# shiftpwm_tlc5916_SMD_RGB.net
KiCad netlist of a schematic drawn in EAGLE
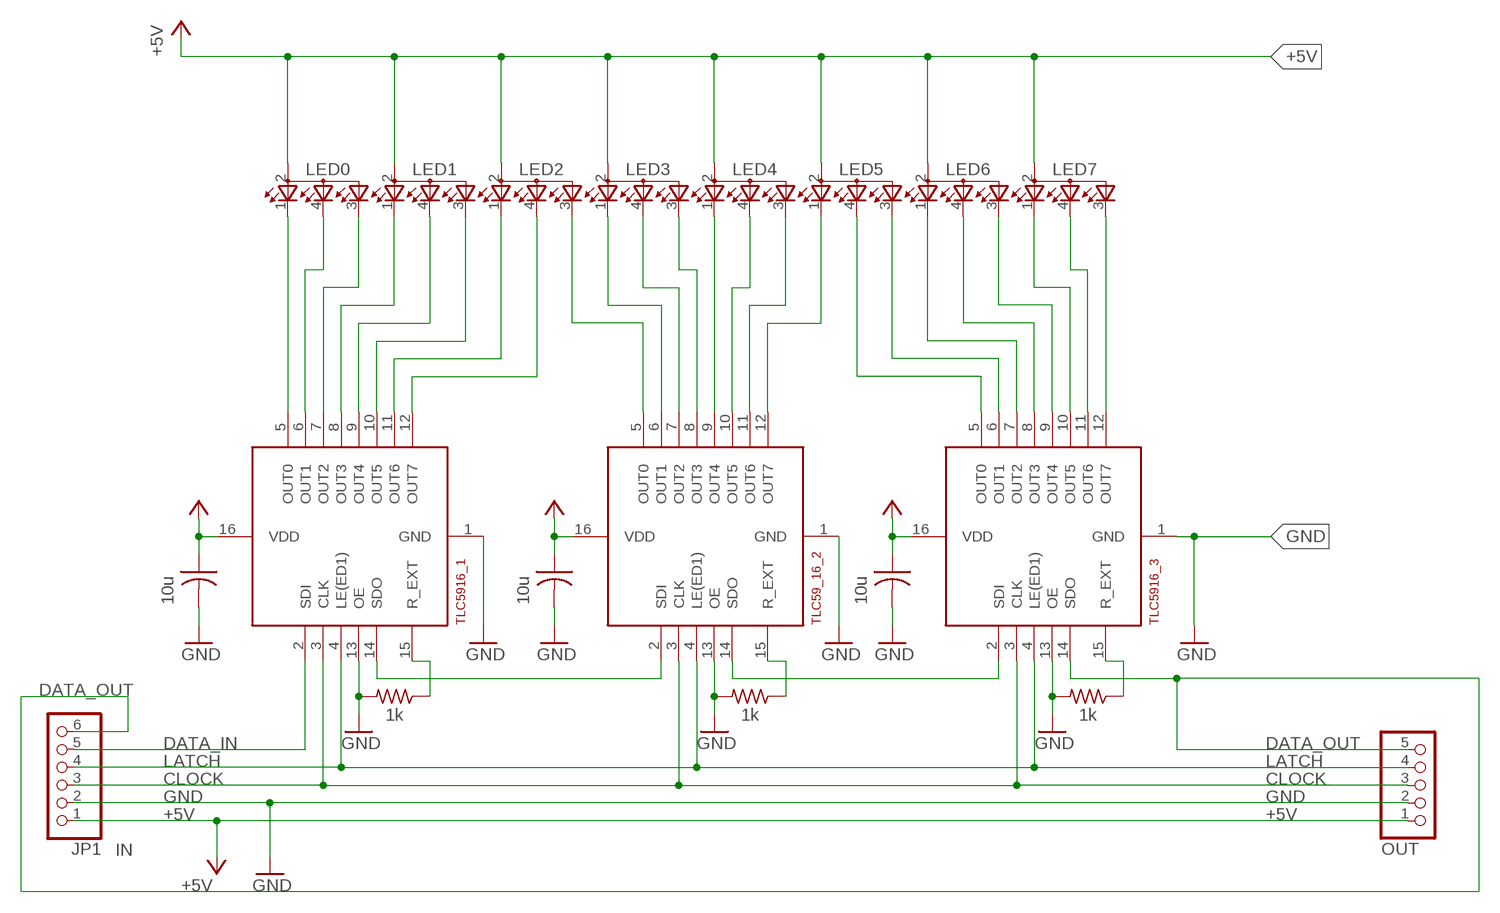
[diagram p0: schematic, sheet 1]

(export (version "E")
  (design (tool "Eeschema 10.0.6"))
  (components
    (comp (ref "C1")
      (value "10u")
      (footprint "eagle-import:C0805K")
      (libsource (lib "eagle-import") (part "C-USC0805K"))
    )
    (comp (ref "C2")
      (value "10u")
      (footprint "eagle-import:C0805K")
      (libsource (lib "eagle-import") (part "C-USC0805K"))
    )
    (comp (ref "C3")
      (value "10u")
      (footprint "eagle-import:C0805K")
      (libsource (lib "eagle-import") (part "C-USC0805K"))
    )
    (comp (ref "JP1")
      (value "IN")
      (footprint "eagle-import:1X06")
      (libsource (lib "eagle-import") (part "PINHD-1X6"))
    )
    (comp (ref "LED0")
      (value "PLLC4-RGB-ELCOSMALL")
      (footprint "eagle-import:P-LCC-4-3-ELCO")
      (libsource (lib "eagle-import") (part "PLLC4-RGB-ELCOSMALL"))
    )
    (comp (ref "LED1")
      (value "PLLC4-RGB-ELCOSMALL")
      (footprint "eagle-import:P-LCC-4-3-ELCO")
      (libsource (lib "eagle-import") (part "PLLC4-RGB-ELCOSMALL"))
    )
    (comp (ref "LED2")
      (value "PLLC4-RGB-ELCOSMALL")
      (footprint "eagle-import:P-LCC-4-3-ELCO")
      (libsource (lib "eagle-import") (part "PLLC4-RGB-ELCOSMALL"))
    )
    (comp (ref "LED3")
      (value "PLLC4-RGB-ELCOSMALL")
      (footprint "eagle-import:P-LCC-4-3-ELCO")
      (libsource (lib "eagle-import") (part "PLLC4-RGB-ELCOSMALL"))
    )
    (comp (ref "LED4")
      (value "PLLC4-RGB-ELCOSMALL")
      (footprint "eagle-import:P-LCC-4-3-ELCO")
      (libsource (lib "eagle-import") (part "PLLC4-RGB-ELCOSMALL"))
    )
    (comp (ref "LED5")
      (value "PLLC4-RGB-ELCOSMALL")
      (footprint "eagle-import:P-LCC-4-3-ELCO")
      (libsource (lib "eagle-import") (part "PLLC4-RGB-ELCOSMALL"))
    )
    (comp (ref "LED6")
      (value "PLLC4-RGB-ELCOSMALL")
      (footprint "eagle-import:P-LCC-4-3-ELCO")
      (libsource (lib "eagle-import") (part "PLLC4-RGB-ELCOSMALL"))
    )
    (comp (ref "LED7")
      (value "PLLC4-RGB-ELCOSMALL")
      (footprint "eagle-import:P-LCC-4-3-ELCO")
      (libsource (lib "eagle-import") (part "PLLC4-RGB-ELCOSMALL"))
    )
    (comp (ref "OUT")
      (value "PINHD-1X5")
      (footprint "eagle-import:1X05")
      (libsource (lib "eagle-import") (part "PINHD-1X5"))
    )
    (comp (ref "R1")
      (value "1k")
      (footprint "eagle-import:R0805")
      (libsource (lib "eagle-import") (part "R-US_R0805"))
    )
    (comp (ref "R2")
      (value "1k")
      (footprint "eagle-import:R0805")
      (libsource (lib "eagle-import") (part "R-US_R0805"))
    )
    (comp (ref "R3")
      (value "1k")
      (footprint "eagle-import:R0805")
      (libsource (lib "eagle-import") (part "R-US_R0805"))
    )
    (comp (ref "TLC59_16_2")
      (value "TLC5916/17")
      (footprint "eagle-import:SOIC-16")
      (libsource (lib "eagle-import") (part "TLC5916/17"))
    )
    (comp (ref "TLC5916_1")
      (value "TLC5916/17")
      (footprint "eagle-import:SOIC-16")
      (libsource (lib "eagle-import") (part "TLC5916/17"))
    )
    (comp (ref "TLC5916_3")
      (value "TLC5916/17")
      (footprint "eagle-import:SOIC-16")
      (libsource (lib "eagle-import") (part "TLC5916/17"))
    )
  )
  (nets
    (net (code "1") (name "+5V") (class "Default")
      (node (ref "C1") (pin "1") (pinfunction "1_1") (pintype "passive"))
      (node (ref "C2") (pin "1") (pinfunction "1_1") (pintype "passive"))
      (node (ref "C3") (pin "1") (pinfunction "1_1") (pintype "passive"))
      (node (ref "JP1") (pin "1") (pinfunction "1_1") (pintype "passive"))
      (node (ref "LED0") (pin "2") (pinfunction "A2_2") (pintype "passive"))
      (node (ref "LED1") (pin "2") (pinfunction "A2_2") (pintype "passive"))
      (node (ref "LED2") (pin "2") (pinfunction "A2_2") (pintype "passive"))
      (node (ref "LED3") (pin "2") (pinfunction "A2_2") (pintype "passive"))
      (node (ref "LED4") (pin "2") (pinfunction "A2_2") (pintype "passive"))
      (node (ref "LED5") (pin "2") (pinfunction "A2_2") (pintype "passive"))
      (node (ref "LED6") (pin "2") (pinfunction "A2_2") (pintype "passive"))
      (node (ref "LED7") (pin "2") (pinfunction "A2_2") (pintype "passive"))
      (node (ref "OUT") (pin "1") (pinfunction "1_1") (pintype "passive"))
      (node (ref "TLC5916_1") (pin "16") (pinfunction "VDD_16") (pintype "bidirectional"))
      (node (ref "TLC5916_3") (pin "16") (pinfunction "VDD_16") (pintype "bidirectional"))
      (node (ref "TLC59_16_2") (pin "16") (pinfunction "VDD_16") (pintype "bidirectional"))
    )
    (net (code "2") (name "/CLOCK") (class "Default")
      (node (ref "JP1") (pin "3") (pinfunction "3_3") (pintype "passive"))
      (node (ref "OUT") (pin "3") (pinfunction "3_3") (pintype "passive"))
      (node (ref "TLC5916_1") (pin "3") (pinfunction "CLK_3") (pintype "bidirectional"))
      (node (ref "TLC5916_3") (pin "3") (pinfunction "CLK_3") (pintype "bidirectional"))
      (node (ref "TLC59_16_2") (pin "3") (pinfunction "CLK_3") (pintype "bidirectional"))
    )
    (net (code "3") (name "/DATA_IN") (class "Default")
      (node (ref "JP1") (pin "5") (pinfunction "5_5") (pintype "passive"))
      (node (ref "TLC5916_1") (pin "2") (pinfunction "SDI_2") (pintype "bidirectional"))
    )
    (net (code "4") (name "/DATA_OUT") (class "Default")
      (node (ref "JP1") (pin "6") (pinfunction "6_6") (pintype "passive"))
      (node (ref "OUT") (pin "5") (pinfunction "5_5") (pintype "passive"))
      (node (ref "TLC5916_3") (pin "14") (pinfunction "SDO_14") (pintype "bidirectional"))
    )
    (net (code "5") (name "/LATCH") (class "Default")
      (node (ref "JP1") (pin "4") (pinfunction "4_4") (pintype "passive"))
      (node (ref "OUT") (pin "4") (pinfunction "4_4") (pintype "passive"))
      (node (ref "TLC5916_1") (pin "4") (pinfunction "LE(ED1)_4") (pintype "bidirectional"))
      (node (ref "TLC5916_3") (pin "4") (pinfunction "LE(ED1)_4") (pintype "bidirectional"))
      (node (ref "TLC59_16_2") (pin "4") (pinfunction "LE(ED1)_4") (pintype "bidirectional"))
    )
    (net (code "6") (name "GND") (class "Default")
      (node (ref "C1") (pin "2") (pinfunction "2_2") (pintype "passive"))
      (node (ref "C2") (pin "2") (pinfunction "2_2") (pintype "passive"))
      (node (ref "C3") (pin "2") (pinfunction "2_2") (pintype "passive"))
      (node (ref "JP1") (pin "2") (pinfunction "2_2") (pintype "passive"))
      (node (ref "OUT") (pin "2") (pinfunction "2_2") (pintype "passive"))
      (node (ref "R1") (pin "2") (pinfunction "2_2") (pintype "passive"))
      (node (ref "R2") (pin "2") (pinfunction "2_2") (pintype "passive"))
      (node (ref "R3") (pin "2") (pinfunction "2_2") (pintype "passive"))
      (node (ref "TLC5916_1") (pin "1") (pinfunction "GND_1") (pintype "bidirectional"))
      (node (ref "TLC5916_1") (pin "13") (pinfunction "OE_13") (pintype "bidirectional"))
      (node (ref "TLC5916_3") (pin "1") (pinfunction "GND_1") (pintype "bidirectional"))
      (node (ref "TLC5916_3") (pin "13") (pinfunction "OE_13") (pintype "bidirectional"))
      (node (ref "TLC59_16_2") (pin "1") (pinfunction "GND_1") (pintype "bidirectional"))
      (node (ref "TLC59_16_2") (pin "13") (pinfunction "OE_13") (pintype "bidirectional"))
    )
    (net (code "7") (name "Net-(LED0-CBLUE)") (class "Default")
      (node (ref "LED0") (pin "3") (pinfunction "CBLUE_3") (pintype "passive"))
      (node (ref "TLC5916_1") (pin "7") (pinfunction "OUT2_7") (pintype "bidirectional"))
    )
    (net (code "8") (name "Net-(LED0-CGREEN)") (class "Default")
      (node (ref "LED0") (pin "4") (pinfunction "CGREEN_4") (pintype "passive"))
      (node (ref "TLC5916_1") (pin "6") (pinfunction "OUT1_6") (pintype "bidirectional"))
    )
    (net (code "9") (name "Net-(LED0-CRED)") (class "Default")
      (node (ref "LED0") (pin "1") (pinfunction "CRED_1") (pintype "passive"))
      (node (ref "TLC5916_1") (pin "5") (pinfunction "OUT0_5") (pintype "bidirectional"))
    )
    (net (code "10") (name "Net-(LED1-CBLUE)") (class "Default")
      (node (ref "LED1") (pin "3") (pinfunction "CBLUE_3") (pintype "passive"))
      (node (ref "TLC5916_1") (pin "10") (pinfunction "OUT5_10") (pintype "bidirectional"))
    )
    (net (code "11") (name "Net-(LED1-CGREEN)") (class "Default")
      (node (ref "LED1") (pin "4") (pinfunction "CGREEN_4") (pintype "passive"))
      (node (ref "TLC5916_1") (pin "9") (pinfunction "OUT4_9") (pintype "bidirectional"))
    )
    (net (code "12") (name "Net-(LED1-CRED)") (class "Default")
      (node (ref "LED1") (pin "1") (pinfunction "CRED_1") (pintype "passive"))
      (node (ref "TLC5916_1") (pin "8") (pinfunction "OUT3_8") (pintype "bidirectional"))
    )
    (net (code "13") (name "Net-(LED2-CBLUE)") (class "Default")
      (node (ref "LED2") (pin "3") (pinfunction "CBLUE_3") (pintype "passive"))
      (node (ref "TLC59_16_2") (pin "5") (pinfunction "OUT0_5") (pintype "bidirectional"))
    )
    (net (code "14") (name "Net-(LED2-CGREEN)") (class "Default")
      (node (ref "LED2") (pin "4") (pinfunction "CGREEN_4") (pintype "passive"))
      (node (ref "TLC5916_1") (pin "12") (pinfunction "OUT7_12") (pintype "bidirectional"))
    )
    (net (code "15") (name "Net-(LED2-CRED)") (class "Default")
      (node (ref "LED2") (pin "1") (pinfunction "CRED_1") (pintype "passive"))
      (node (ref "TLC5916_1") (pin "11") (pinfunction "OUT6_11") (pintype "bidirectional"))
    )
    (net (code "16") (name "Net-(LED3-CBLUE)") (class "Default")
      (node (ref "LED3") (pin "3") (pinfunction "CBLUE_3") (pintype "passive"))
      (node (ref "TLC59_16_2") (pin "8") (pinfunction "OUT3_8") (pintype "bidirectional"))
    )
    (net (code "17") (name "Net-(LED3-CGREEN)") (class "Default")
      (node (ref "LED3") (pin "4") (pinfunction "CGREEN_4") (pintype "passive"))
      (node (ref "TLC59_16_2") (pin "7") (pinfunction "OUT2_7") (pintype "bidirectional"))
    )
    (net (code "18") (name "Net-(LED3-CRED)") (class "Default")
      (node (ref "LED3") (pin "1") (pinfunction "CRED_1") (pintype "passive"))
      (node (ref "TLC59_16_2") (pin "6") (pinfunction "OUT1_6") (pintype "bidirectional"))
    )
    (net (code "19") (name "Net-(LED4-CBLUE)") (class "Default")
      (node (ref "LED4") (pin "3") (pinfunction "CBLUE_3") (pintype "passive"))
      (node (ref "TLC59_16_2") (pin "11") (pinfunction "OUT6_11") (pintype "bidirectional"))
    )
    (net (code "20") (name "Net-(LED4-CGREEN)") (class "Default")
      (node (ref "LED4") (pin "4") (pinfunction "CGREEN_4") (pintype "passive"))
      (node (ref "TLC59_16_2") (pin "10") (pinfunction "OUT5_10") (pintype "bidirectional"))
    )
    (net (code "21") (name "Net-(LED4-CRED)") (class "Default")
      (node (ref "LED4") (pin "1") (pinfunction "CRED_1") (pintype "passive"))
      (node (ref "TLC59_16_2") (pin "9") (pinfunction "OUT4_9") (pintype "bidirectional"))
    )
    (net (code "22") (name "Net-(LED5-CBLUE)") (class "Default")
      (node (ref "LED5") (pin "3") (pinfunction "CBLUE_3") (pintype "passive"))
      (node (ref "TLC5916_3") (pin "6") (pinfunction "OUT1_6") (pintype "bidirectional"))
    )
    (net (code "23") (name "Net-(LED5-CGREEN)") (class "Default")
      (node (ref "LED5") (pin "4") (pinfunction "CGREEN_4") (pintype "passive"))
      (node (ref "TLC5916_3") (pin "5") (pinfunction "OUT0_5") (pintype "bidirectional"))
    )
    (net (code "24") (name "Net-(LED5-CRED)") (class "Default")
      (node (ref "LED5") (pin "1") (pinfunction "CRED_1") (pintype "passive"))
      (node (ref "TLC59_16_2") (pin "12") (pinfunction "OUT7_12") (pintype "bidirectional"))
    )
    (net (code "25") (name "Net-(LED6-CBLUE)") (class "Default")
      (node (ref "LED6") (pin "3") (pinfunction "CBLUE_3") (pintype "passive"))
      (node (ref "TLC5916_3") (pin "9") (pinfunction "OUT4_9") (pintype "bidirectional"))
    )
    (net (code "26") (name "Net-(LED6-CGREEN)") (class "Default")
      (node (ref "LED6") (pin "4") (pinfunction "CGREEN_4") (pintype "passive"))
      (node (ref "TLC5916_3") (pin "8") (pinfunction "OUT3_8") (pintype "bidirectional"))
    )
    (net (code "27") (name "Net-(LED6-CRED)") (class "Default")
      (node (ref "LED6") (pin "1") (pinfunction "CRED_1") (pintype "passive"))
      (node (ref "TLC5916_3") (pin "7") (pinfunction "OUT2_7") (pintype "bidirectional"))
    )
    (net (code "28") (name "Net-(LED7-CBLUE)") (class "Default")
      (node (ref "LED7") (pin "3") (pinfunction "CBLUE_3") (pintype "passive"))
      (node (ref "TLC5916_3") (pin "12") (pinfunction "OUT7_12") (pintype "bidirectional"))
    )
    (net (code "29") (name "Net-(LED7-CGREEN)") (class "Default")
      (node (ref "LED7") (pin "4") (pinfunction "CGREEN_4") (pintype "passive"))
      (node (ref "TLC5916_3") (pin "11") (pinfunction "OUT6_11") (pintype "bidirectional"))
    )
    (net (code "30") (name "Net-(LED7-CRED)") (class "Default")
      (node (ref "LED7") (pin "1") (pinfunction "CRED_1") (pintype "passive"))
      (node (ref "TLC5916_3") (pin "10") (pinfunction "OUT5_10") (pintype "bidirectional"))
    )
    (net (code "31") (name "Net-(TLC59_16_2-R_EXT)") (class "Default")
      (node (ref "R2") (pin "1") (pinfunction "1_1") (pintype "passive"))
      (node (ref "TLC59_16_2") (pin "15") (pinfunction "R_EXT_15") (pintype "bidirectional"))
    )
    (net (code "32") (name "Net-(TLC5916_1-R_EXT)") (class "Default")
      (node (ref "R1") (pin "1") (pinfunction "1_1") (pintype "passive"))
      (node (ref "TLC5916_1") (pin "15") (pinfunction "R_EXT_15") (pintype "bidirectional"))
    )
    (net (code "33") (name "Net-(TLC5916_1-SDO)") (class "Default")
      (node (ref "TLC5916_1") (pin "14") (pinfunction "SDO_14") (pintype "bidirectional"))
      (node (ref "TLC59_16_2") (pin "2") (pinfunction "SDI_2") (pintype "bidirectional"))
    )
    (net (code "34") (name "Net-(TLC5916_3-R_EXT)") (class "Default")
      (node (ref "R3") (pin "1") (pinfunction "1_1") (pintype "passive"))
      (node (ref "TLC5916_3") (pin "15") (pinfunction "R_EXT_15") (pintype "bidirectional"))
    )
    (net (code "35") (name "Net-(TLC5916_3-SDI)") (class "Default")
      (node (ref "TLC5916_3") (pin "2") (pinfunction "SDI_2") (pintype "bidirectional"))
      (node (ref "TLC59_16_2") (pin "14") (pinfunction "SDO_14") (pintype "bidirectional"))
    )
  )
)
